# touringmach3.net
KiCad netlist of a schematic drawn in EAGLE
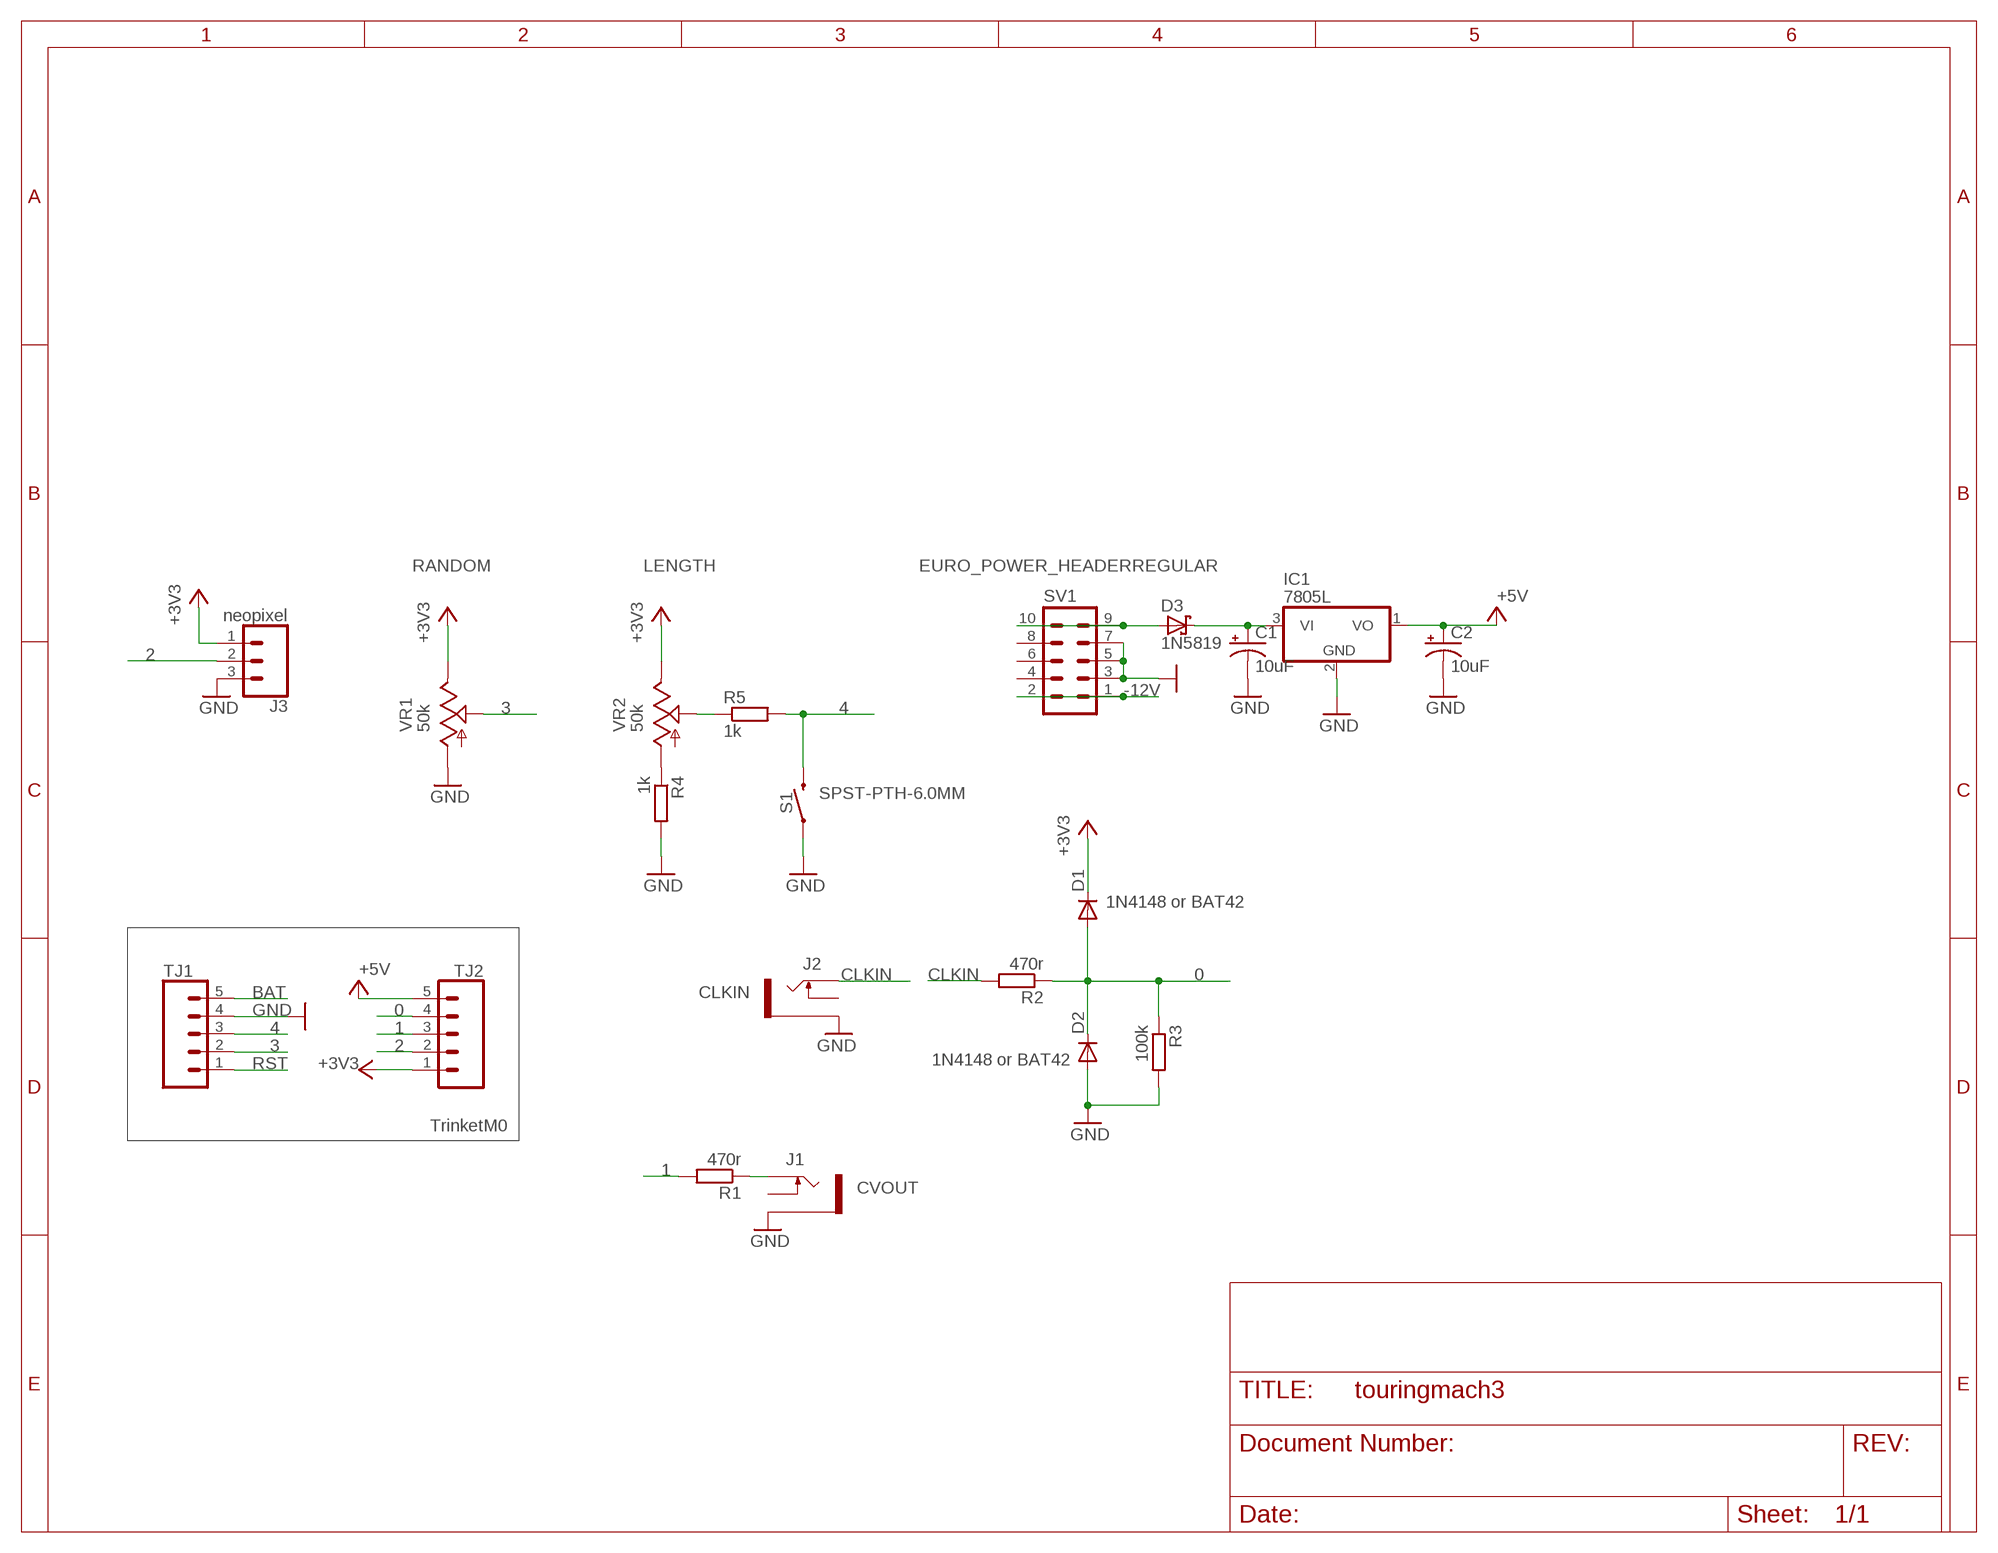
[diagram p0: schematic, sheet 1]

(export (version "E")
  (design (tool "Eeschema 10.0.6"))
  (components
    (comp (ref "C1")
      (value "10uF")
      (footprint "eagle-import:E2,5-6")
      (libsource (lib "eagle-import") (part "CPOL-USE2.5-6"))
    )
    (comp (ref "C2")
      (value "10uF")
      (footprint "eagle-import:E2,5-6")
      (libsource (lib "eagle-import") (part "CPOL-USE2.5-6"))
    )
    (comp (ref "D1")
      (value "1N4148 or BAT42")
      (footprint "eagle-import:DO34-7")
      (libsource (lib "eagle-import") (part "BAT42"))
    )
    (comp (ref "D2")
      (value "1N4148 or BAT42")
      (footprint "eagle-import:DO34-7")
      (libsource (lib "eagle-import") (part "BAT42"))
    )
    (comp (ref "D3")
      (value "1N5819")
      (footprint "eagle-import:DO41-7.6")
      (libsource (lib "eagle-import") (part "1N5819-B"))
    )
    (comp (ref "IC1")
      (value "7805L")
      (footprint "eagle-import:TO92")
      (libsource (lib "eagle-import") (part "78L05"))
    )
    (comp (ref "J1")
      (value "THONKICONNOLD")
      (footprint "eagle-import:THONKICONN")
      (libsource (lib "eagle-import") (part "THONKICONNOLD"))
    )
    (comp (ref "J2")
      (value "THONKICONNOLD")
      (footprint "eagle-import:THONKICONN")
      (libsource (lib "eagle-import") (part "THONKICONNOLD"))
    )
    (comp (ref "J3")
      (value "neopixel")
      (footprint "eagle-import:1X03")
      (libsource (lib "eagle-import") (part "CONN_03"))
    )
    (comp (ref "R1")
      (value "470r")
      (footprint "eagle-import:7MM_RESISTOR")
      (libsource (lib "eagle-import") (part "RESISTOR7MM"))
    )
    (comp (ref "R2")
      (value "470r")
      (footprint "eagle-import:7MM_RESISTOR")
      (libsource (lib "eagle-import") (part "RESISTOR7MM"))
    )
    (comp (ref "R3")
      (value "100k")
      (footprint "eagle-import:7MM_RESISTOR")
      (libsource (lib "eagle-import") (part "RESISTOR7MM"))
    )
    (comp (ref "R4")
      (value "1k")
      (footprint "eagle-import:7MM_RESISTOR")
      (libsource (lib "eagle-import") (part "RESISTOR7MM"))
    )
    (comp (ref "R5")
      (value "1k")
      (footprint "eagle-import:7MM_RESISTOR")
      (libsource (lib "eagle-import") (part "RESISTOR7MM"))
    )
    (comp (ref "S1")
      (value "SPST-PTH-6.0MM")
      (footprint "eagle-import:TACTILE_SWITCH_PTH_6.0MM")
      (libsource (lib "eagle-import") (part "MOMENTARY-SWITCH-SPST-PTH-6.0MM"))
    )
    (comp (ref "SV1")
      (value "EURO_POWER_HEADERREGULAR")
      (footprint "eagle-import:EURO_POWER_HEADER")
      (libsource (lib "eagle-import") (part "EURO_POWER_HEADERREGULAR"))
    )
    (comp (ref "TJ1")
      (value "CONN_05")
      (footprint "eagle-import:1X05")
      (libsource (lib "eagle-import") (part "CONN_05"))
    )
    (comp (ref "TJ2")
      (value "CONN_05")
      (footprint "eagle-import:1X05")
      (libsource (lib "eagle-import") (part "CONN_05"))
    )
    (comp (ref "VR1")
      (value "50k")
      (footprint "eagle-import:9MM_SNAP-IN_POT")
      (libsource (lib "eagle-import") (part "9MM_SNAP-IN_POT_"))
    )
    (comp (ref "VR2")
      (value "50k")
      (footprint "eagle-import:9MM_SNAP-IN_POT")
      (libsource (lib "eagle-import") (part "9MM_SNAP-IN_POT_"))
    )
  )
  (nets
    (net (code "1") (name "+3V3") (class "Default")
      (node (ref "D1") (pin "C") (pinfunction "C_C") (pintype "passive"))
      (node (ref "J3") (pin "1") (pinfunction "1_1") (pintype "passive"))
      (node (ref "TJ2") (pin "1") (pinfunction "1_1") (pintype "passive"))
      (node (ref "VR1") (pin "3") (pinfunction "E_3") (pintype "passive"))
      (node (ref "VR2") (pin "3") (pinfunction "E_3") (pintype "passive"))
    )
    (net (code "2") (name "+5V") (class "Default")
      (node (ref "C2") (pin "+") (pinfunction "+_+") (pintype "passive"))
      (node (ref "IC1") (pin "1") (pinfunction "VO_1") (pintype "passive"))
      (node (ref "TJ2") (pin "5") (pinfunction "5_5") (pintype "passive"))
    )
    (net (code "3") (name "/-12V") (class "Default")
      (node (ref "SV1") (pin "1") (pinfunction "1_1") (pintype "passive"))
      (node (ref "SV1") (pin "2") (pinfunction "2_2") (pintype "passive"))
    )
    (net (code "4") (name "/0") (class "Default")
      (node (ref "D1") (pin "A") (pinfunction "A_A") (pintype "passive"))
      (node (ref "D2") (pin "C") (pinfunction "C_C") (pintype "passive"))
      (node (ref "R2") (pin "1") (pinfunction "1_1") (pintype "passive"))
      (node (ref "R3") (pin "1") (pinfunction "1_1") (pintype "passive"))
      (node (ref "TJ2") (pin "4") (pinfunction "4_4") (pintype "passive"))
    )
    (net (code "5") (name "/1") (class "Default")
      (node (ref "R1") (pin "2") (pinfunction "2_2") (pintype "passive"))
      (node (ref "TJ2") (pin "3") (pinfunction "3_3") (pintype "passive"))
    )
    (net (code "6") (name "/2") (class "Default")
      (node (ref "J3") (pin "2") (pinfunction "2_2") (pintype "passive"))
      (node (ref "TJ2") (pin "2") (pinfunction "2_2") (pintype "passive"))
    )
    (net (code "7") (name "/3") (class "Default")
      (node (ref "TJ1") (pin "2") (pinfunction "2_2") (pintype "passive"))
      (node (ref "VR1") (pin "2") (pinfunction "S_2") (pintype "passive"))
    )
    (net (code "8") (name "/4") (class "Default")
      (node (ref "R5") (pin "2") (pinfunction "2_2") (pintype "passive"))
      (node (ref "S1") (pin "3") (pinfunction "2_3") (pintype "passive"))
      (node (ref "TJ1") (pin "3") (pinfunction "3_3") (pintype "passive"))
    )
    (net (code "9") (name "/BAT") (class "Default")
      (node (ref "TJ1") (pin "5") (pinfunction "5_5") (pintype "passive"))
    )
    (net (code "10") (name "/CLKIN") (class "Default")
      (node (ref "J2") (pin "P$3_TIP") (pinfunction "TIP_P$3_TIP") (pintype "passive"))
      (node (ref "R2") (pin "2") (pinfunction "2_2") (pintype "passive"))
    )
    (net (code "11") (name "/RST") (class "Default")
      (node (ref "TJ1") (pin "1") (pinfunction "1_1") (pintype "passive"))
    )
    (net (code "12") (name "GND") (class "Default")
      (node (ref "C1") (pin "-") (pinfunction "-_-") (pintype "passive"))
      (node (ref "C2") (pin "-") (pinfunction "-_-") (pintype "passive"))
      (node (ref "D2") (pin "A") (pinfunction "A_A") (pintype "passive"))
      (node (ref "IC1") (pin "2") (pinfunction "GND_2") (pintype "passive"))
      (node (ref "J1") (pin "P$1_SLEEVE") (pinfunction "SLEEVE_P$1_SLEEVE") (pintype "passive"))
      (node (ref "J2") (pin "P$1_SLEEVE") (pinfunction "SLEEVE_P$1_SLEEVE") (pintype "passive"))
      (node (ref "J3") (pin "3") (pinfunction "3_3") (pintype "passive"))
      (node (ref "R3") (pin "2") (pinfunction "2_2") (pintype "passive"))
      (node (ref "R4") (pin "2") (pinfunction "2_2") (pintype "passive"))
      (node (ref "S1") (pin "1") (pinfunction "1_1") (pintype "passive"))
      (node (ref "SV1") (pin "3") (pinfunction "3_3") (pintype "passive"))
      (node (ref "SV1") (pin "5") (pinfunction "5_5") (pintype "passive"))
      (node (ref "SV1") (pin "7") (pinfunction "7_7") (pintype "passive"))
      (node (ref "TJ1") (pin "4") (pinfunction "4_4") (pintype "passive"))
      (node (ref "VR1") (pin "1") (pinfunction "A_1") (pintype "passive"))
    )
    (net (code "13") (name "Net-(D3-PadA)") (class "Default")
      (node (ref "D3") (pin "A") (pinfunction "A_A") (pintype "passive"))
      (node (ref "SV1") (pin "10") (pinfunction "10_10") (pintype "passive"))
      (node (ref "SV1") (pin "9") (pinfunction "9_9") (pintype "passive"))
    )
    (net (code "14") (name "Net-(IC1-VI)") (class "Default")
      (node (ref "C1") (pin "+") (pinfunction "+_+") (pintype "passive"))
      (node (ref "D3") (pin "C") (pinfunction "C_C") (pintype "passive"))
      (node (ref "IC1") (pin "3") (pinfunction "VI_3") (pintype "input"))
    )
    (net (code "15") (name "Net-(J1-TIP)") (class "Default")
      (node (ref "J1") (pin "P$3_TIP") (pinfunction "TIP_P$3_TIP") (pintype "passive"))
      (node (ref "R1") (pin "1") (pinfunction "1_1") (pintype "passive"))
    )
    (net (code "16") (name "Net-(VR2-A)") (class "Default")
      (node (ref "R4") (pin "1") (pinfunction "1_1") (pintype "passive"))
      (node (ref "VR2") (pin "1") (pinfunction "A_1") (pintype "passive"))
    )
    (net (code "17") (name "Net-(VR2-S)") (class "Default")
      (node (ref "R5") (pin "1") (pinfunction "1_1") (pintype "passive"))
      (node (ref "VR2") (pin "2") (pinfunction "S_2") (pintype "passive"))
    )
    (net (code "18") (name "unconnected-(J1-SWITCH-PadP$2_SWITCH)") (class "Default")
      (node (ref "J1") (pin "P$2_SWITCH") (pinfunction "SWITCH_P$2_SWITCH") (pintype "passive"))
    )
    (net (code "19") (name "unconnected-(J2-SWITCH-PadP$2_SWITCH)") (class "Default")
      (node (ref "J2") (pin "P$2_SWITCH") (pinfunction "SWITCH_P$2_SWITCH") (pintype "passive"))
    )
    (net (code "20") (name "unconnected-(SV1-Pad4)") (class "Default")
      (node (ref "SV1") (pin "4") (pinfunction "4_4") (pintype "passive"))
    )
    (net (code "21") (name "unconnected-(SV1-Pad6)") (class "Default")
      (node (ref "SV1") (pin "6") (pinfunction "6_6") (pintype "passive"))
    )
    (net (code "22") (name "unconnected-(SV1-Pad8)") (class "Default")
      (node (ref "SV1") (pin "8") (pinfunction "8_8") (pintype "passive"))
    )
  )
)
